# LickStick_v0_3.net
KiCad netlist of a schematic drawn in EAGLE
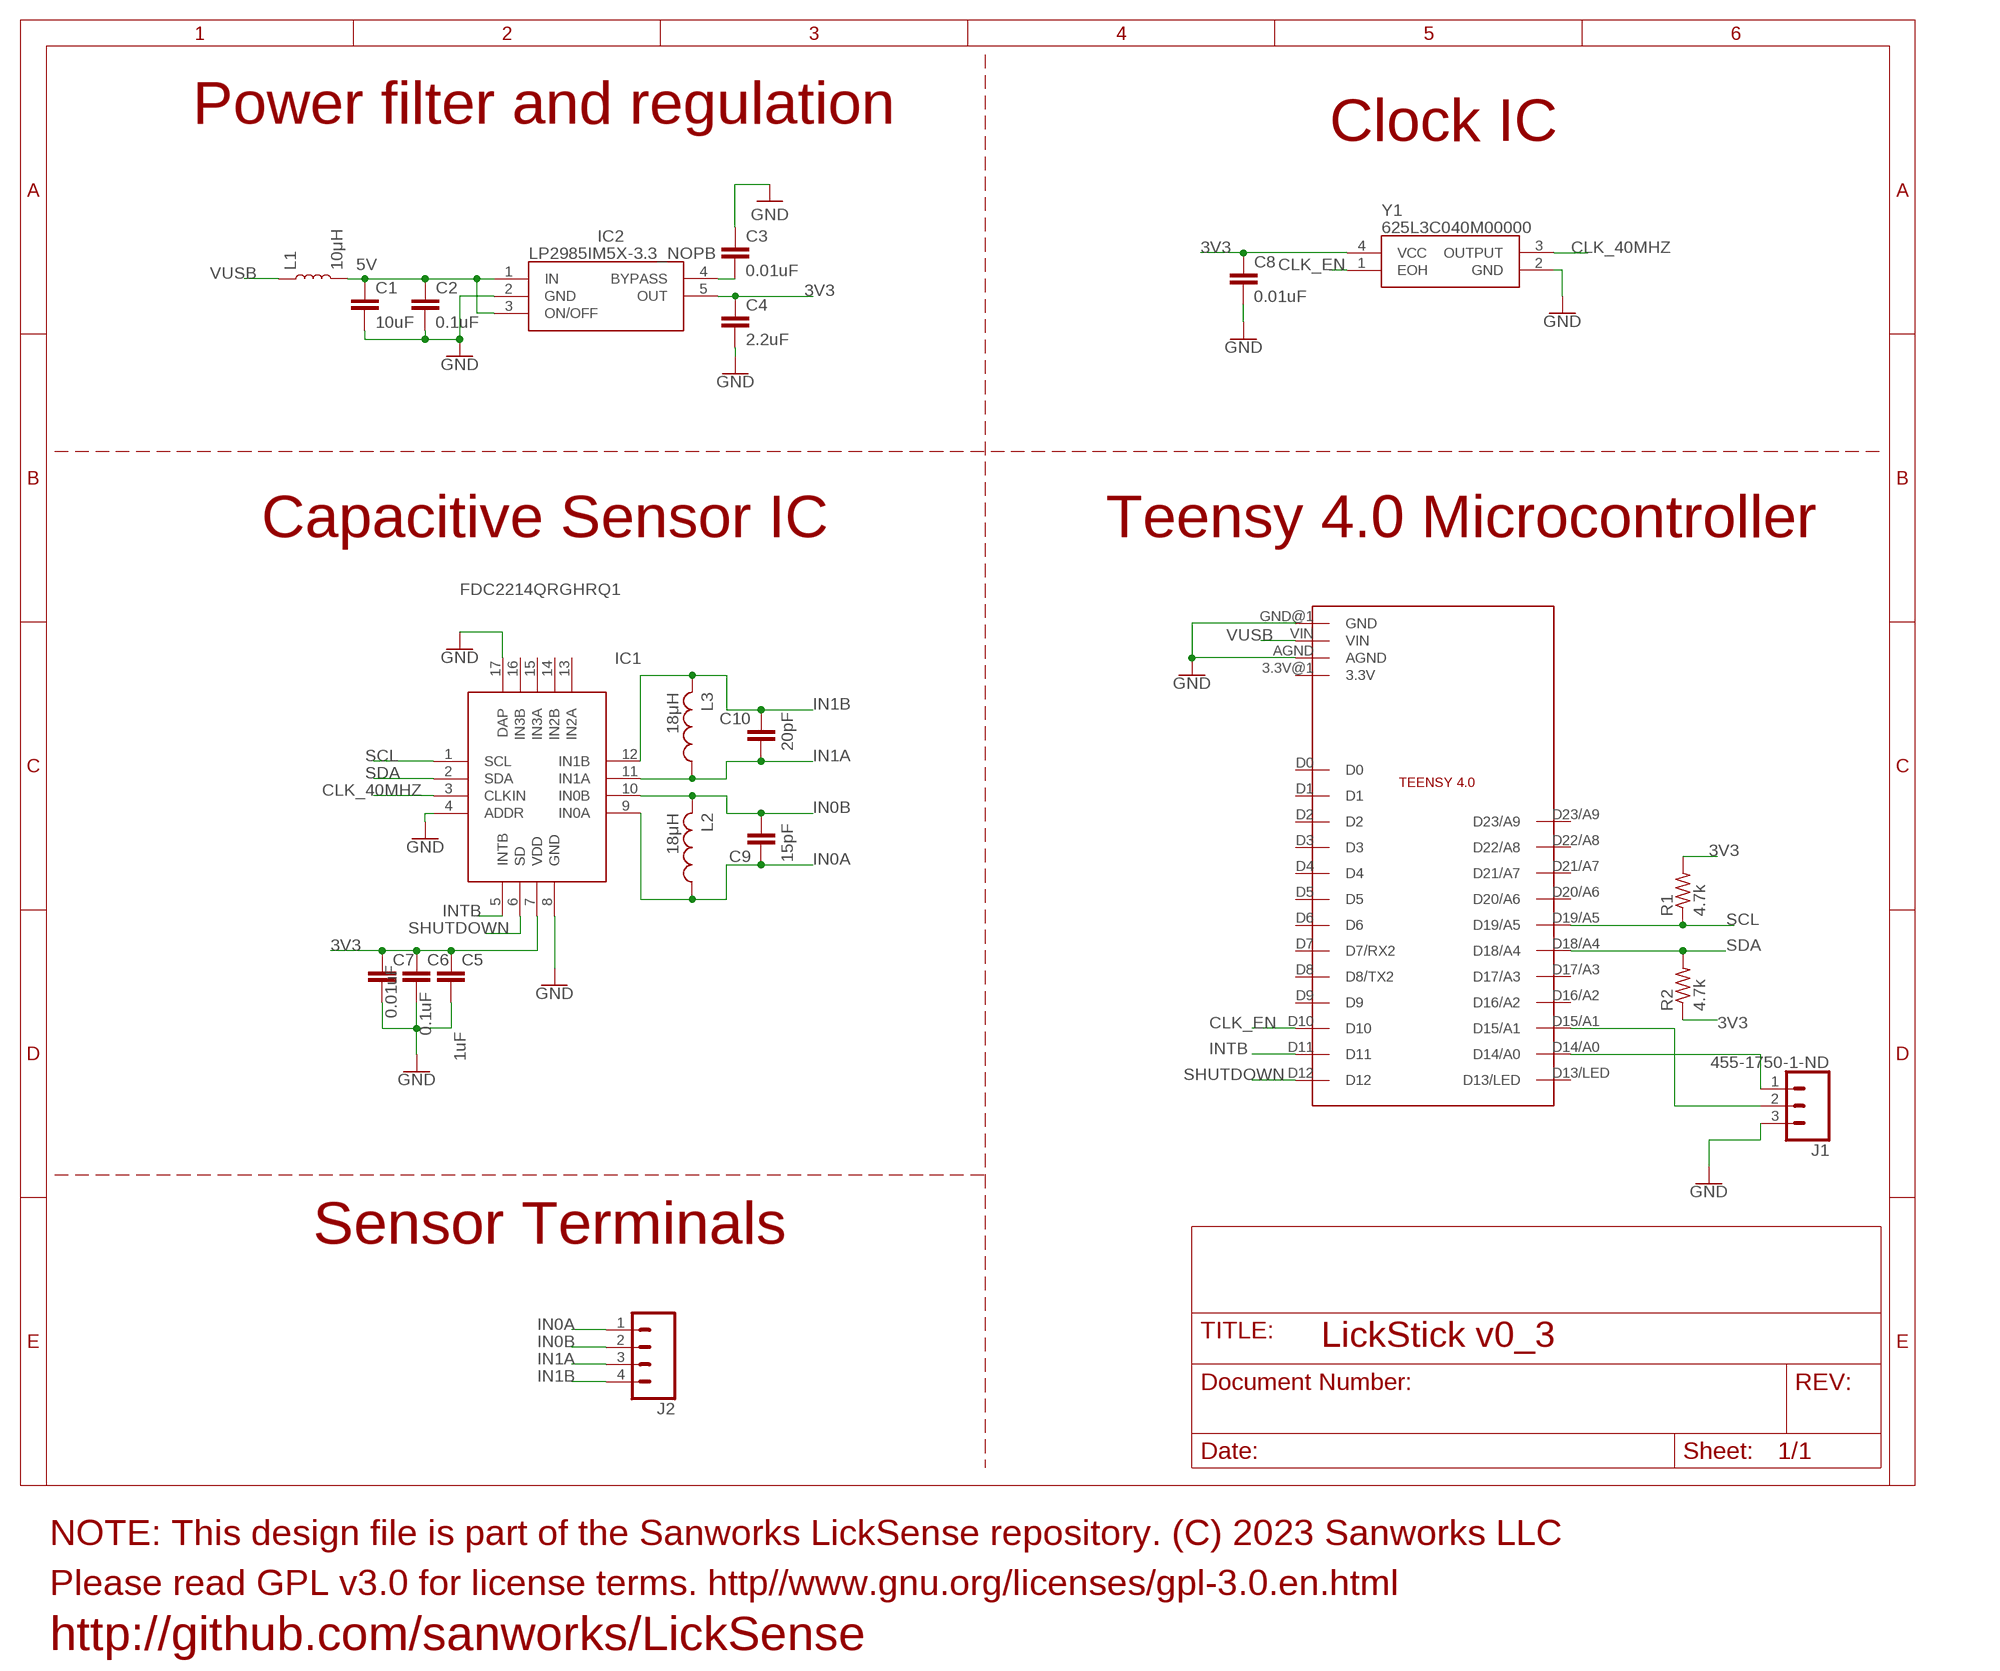
[diagram p0: schematic, sheet 1]

(export (version "E")
  (design (tool "Eeschema 10.0.6"))
  (components
    (comp (ref "C1")
      (value "10uF")
      (footprint "eagle-import:0805")
      (libsource (lib "eagle-import") (part "10UF-0805-10V-10%"))
    )
    (comp (ref "C2")
      (value "0.1uF")
      (footprint "eagle-import:0805")
      (libsource (lib "eagle-import") (part "1.0UF-0805-25V-(+80/-20%)"))
    )
    (comp (ref "C3")
      (value "0.01uF")
      (footprint "eagle-import:0805")
      (libsource (lib "eagle-import") (part "1.0UF-0805-25V-(+80/-20%)"))
    )
    (comp (ref "C4")
      (value "2.2uF")
      (footprint "eagle-import:0805")
      (libsource (lib "eagle-import") (part "1.0UF-0805-25V-(+80/-20%)"))
    )
    (comp (ref "C5")
      (value "1uF")
      (footprint "eagle-import:0805")
      (libsource (lib "eagle-import") (part "1.0UF-0805-25V-(+80/-20%)"))
    )
    (comp (ref "C6")
      (value "0.1uF")
      (footprint "eagle-import:0805")
      (libsource (lib "eagle-import") (part "1.0UF-0805-25V-(+80/-20%)"))
    )
    (comp (ref "C7")
      (value "0.01uF")
      (footprint "eagle-import:0805")
      (libsource (lib "eagle-import") (part "1.0UF-0805-25V-(+80/-20%)"))
    )
    (comp (ref "C8")
      (value "0.01uF")
      (footprint "eagle-import:0805")
      (libsource (lib "eagle-import") (part "1.0UF-0805-25V-(+80/-20%)"))
    )
    (comp (ref "C9")
      (value "15pF")
      (footprint "eagle-import:0805")
      (libsource (lib "eagle-import") (part "1.0UF-0805-25V-(+80/-20%)"))
    )
    (comp (ref "C10")
      (value "20pF")
      (footprint "eagle-import:0805")
      (libsource (lib "eagle-import") (part "1.0UF-0805-25V-(+80/-20%)"))
    )
    (comp (ref "IC1")
      (value "FDC2214QRGHRQ1")
      (footprint "eagle-import:QFN50P400X400X80-17N")
      (fields (field (name "MOUSER_PART_NUMBER") "595-FDC2214QRGHRQ1"))
      (libsource (lib "eagle-import") (part "FDC2214QRGHRQ1"))
    )
    (comp (ref "IC2")
      (value "LP2985IM5X-3.3_NOPB")
      (footprint "eagle-import:SOT95P280X145-5N")
      (fields
        (field (name "MANUFACTURER_PART_NUMBER") "LP2985IM5X-3.3/NOPB")
        (field (name "MOUSER_PART_NUMBER") "926-LP2985IM5X33NOPB")
      )
      (libsource (lib "eagle-import") (part "LP2985IM5X-3.3_NOPB"))
    )
    (comp (ref "J1")
      (value "455-1750-1-ND")
      (footprint "eagle-import:1X03")
      (libsource (lib "eagle-import") (part "CONN_03"))
    )
    (comp (ref "J2")
      (value "CONN_04PTH")
      (footprint "eagle-import:1X04")
      (libsource (lib "eagle-import") (part "CONN_04PTH"))
    )
    (comp (ref "L1")
      (value "10μH")
      (footprint "eagle-import:0806")
      (libsource (lib "eagle-import") (part "2.2μH_SHIELDED_INDUCTOR"))
    )
    (comp (ref "L2")
      (value "18μH")
      (footprint "eagle-import:L3225P")
      (libsource (lib "eagle-import") (part "L-USL3225P"))
    )
    (comp (ref "L3")
      (value "18μH")
      (footprint "eagle-import:L3225P")
      (libsource (lib "eagle-import") (part "L-USL3225P"))
    )
    (comp (ref "MC1")
      (value "TEENSY4.0_SIMPLE_NO_VUSB")
      (footprint "eagle-import:TEENSY4.0_SIMPLE_NO_VUSB")
      (libsource (lib "eagle-import") (part "TEENSY4.0_SIMPLE_NO_VUSB"))
    )
    (comp (ref "R1")
      (value "4.7k")
      (footprint "eagle-import:R0805")
      (libsource (lib "eagle-import") (part "R-US_R0805"))
    )
    (comp (ref "R2")
      (value "4.7k")
      (footprint "eagle-import:R0805")
      (libsource (lib "eagle-import") (part "R-US_R0805"))
    )
    (comp (ref "Y1")
      (value "625L3C040M00000")
      (footprint "eagle-import:625L3C040M00000")
      (fields (field (name "MOUSER_PART_NUMBER") "774-625L3C040M00000"))
      (libsource (lib "eagle-import") (part "625L3C040M00000"))
    )
  )
  (nets
    (net (code "1") (name "/3V3") (class "Default")
      (node (ref "C4") (pin "1") (pinfunction "1_1") (pintype "passive"))
      (node (ref "C5") (pin "1") (pinfunction "1_1") (pintype "passive"))
      (node (ref "C6") (pin "1") (pinfunction "1_1") (pintype "passive"))
      (node (ref "C7") (pin "1") (pinfunction "1_1") (pintype "passive"))
      (node (ref "C8") (pin "1") (pinfunction "1_1") (pintype "passive"))
      (node (ref "IC1") (pin "7") (pinfunction "VDD_7") (pintype "bidirectional"))
      (node (ref "IC2") (pin "5") (pinfunction "OUT_5") (pintype "bidirectional"))
      (node (ref "R1") (pin "2") (pinfunction "2_2") (pintype "passive"))
      (node (ref "R2") (pin "1") (pinfunction "1_1") (pintype "passive"))
      (node (ref "Y1") (pin "4") (pinfunction "VCC_4") (pintype "bidirectional"))
    )
    (net (code "2") (name "/5V") (class "Default")
      (node (ref "C1") (pin "1") (pinfunction "1_1") (pintype "passive"))
      (node (ref "C2") (pin "1") (pinfunction "1_1") (pintype "passive"))
      (node (ref "IC2") (pin "1") (pinfunction "IN_1") (pintype "bidirectional"))
      (node (ref "IC2") (pin "3") (pinfunction "ON/OFF_3") (pintype "bidirectional"))
      (node (ref "L1") (pin "2") (pinfunction "2_2") (pintype "passive"))
    )
    (net (code "3") (name "/CLK_40MHZ") (class "Default")
      (node (ref "IC1") (pin "3") (pinfunction "CLKIN_3") (pintype "bidirectional"))
      (node (ref "Y1") (pin "3") (pinfunction "OUTPUT_3") (pintype "bidirectional"))
    )
    (net (code "4") (name "/CLK_EN") (class "Default")
      (node (ref "MC1") (pin "D10") (pinfunction "D10_D10") (pintype "bidirectional"))
      (node (ref "Y1") (pin "1") (pinfunction "EOH_1") (pintype "bidirectional"))
    )
    (net (code "5") (name "/IN0A") (class "Default")
      (node (ref "C9") (pin "1") (pinfunction "1_1") (pintype "passive"))
      (node (ref "IC1") (pin "9") (pinfunction "IN0A_9") (pintype "bidirectional"))
      (node (ref "J2") (pin "1") (pinfunction "1_1") (pintype "passive"))
      (node (ref "L2") (pin "1") (pinfunction "1_1") (pintype "passive"))
    )
    (net (code "6") (name "/IN0B") (class "Default")
      (node (ref "C9") (pin "2") (pinfunction "2_2") (pintype "passive"))
      (node (ref "IC1") (pin "10") (pinfunction "IN0B_10") (pintype "bidirectional"))
      (node (ref "J2") (pin "2") (pinfunction "2_2") (pintype "passive"))
      (node (ref "L2") (pin "2") (pinfunction "2_2") (pintype "passive"))
    )
    (net (code "7") (name "/IN1A") (class "Default")
      (node (ref "C10") (pin "1") (pinfunction "1_1") (pintype "passive"))
      (node (ref "IC1") (pin "11") (pinfunction "IN1A_11") (pintype "bidirectional"))
      (node (ref "J2") (pin "3") (pinfunction "3_3") (pintype "passive"))
      (node (ref "L3") (pin "1") (pinfunction "1_1") (pintype "passive"))
    )
    (net (code "8") (name "/IN1B") (class "Default")
      (node (ref "C10") (pin "2") (pinfunction "2_2") (pintype "passive"))
      (node (ref "IC1") (pin "12") (pinfunction "IN1B_12") (pintype "bidirectional"))
      (node (ref "J2") (pin "4") (pinfunction "4_4") (pintype "passive"))
      (node (ref "L3") (pin "2") (pinfunction "2_2") (pintype "passive"))
    )
    (net (code "9") (name "/INTB") (class "Default")
      (node (ref "IC1") (pin "5") (pinfunction "INTB_5") (pintype "bidirectional"))
      (node (ref "MC1") (pin "D11") (pinfunction "D11_D11") (pintype "bidirectional"))
    )
    (net (code "10") (name "/SCL") (class "Default")
      (node (ref "IC1") (pin "1") (pinfunction "SCL_1") (pintype "bidirectional"))
      (node (ref "MC1") (pin "D19/A5") (pinfunction "D19/A5_D19/A5") (pintype "bidirectional"))
      (node (ref "R1") (pin "1") (pinfunction "1_1") (pintype "passive"))
    )
    (net (code "11") (name "/SDA") (class "Default")
      (node (ref "IC1") (pin "2") (pinfunction "SDA_2") (pintype "bidirectional"))
      (node (ref "MC1") (pin "D18/A4") (pinfunction "D18/A4_D18/A4") (pintype "bidirectional"))
      (node (ref "R2") (pin "2") (pinfunction "2_2") (pintype "passive"))
    )
    (net (code "12") (name "/SHUTDOWN") (class "Default")
      (node (ref "IC1") (pin "6") (pinfunction "SD_6") (pintype "bidirectional"))
      (node (ref "MC1") (pin "D12") (pinfunction "D12_D12") (pintype "bidirectional"))
    )
    (net (code "13") (name "/VUSB") (class "Default")
      (node (ref "L1") (pin "1") (pinfunction "1_1") (pintype "passive"))
      (node (ref "MC1") (pin "VIN") (pinfunction "VIN_VIN") (pintype "bidirectional"))
    )
    (net (code "14") (name "GND") (class "Default")
      (node (ref "C1") (pin "2") (pinfunction "2_2") (pintype "passive"))
      (node (ref "C2") (pin "2") (pinfunction "2_2") (pintype "passive"))
      (node (ref "C3") (pin "1") (pinfunction "1_1") (pintype "passive"))
      (node (ref "C4") (pin "2") (pinfunction "2_2") (pintype "passive"))
      (node (ref "C5") (pin "2") (pinfunction "2_2") (pintype "passive"))
      (node (ref "C6") (pin "2") (pinfunction "2_2") (pintype "passive"))
      (node (ref "C7") (pin "2") (pinfunction "2_2") (pintype "passive"))
      (node (ref "C8") (pin "2") (pinfunction "2_2") (pintype "passive"))
      (node (ref "IC1") (pin "17") (pinfunction "DAP_17") (pintype "bidirectional"))
      (node (ref "IC1") (pin "4") (pinfunction "ADDR_4") (pintype "bidirectional"))
      (node (ref "IC1") (pin "8") (pinfunction "GND_8") (pintype "bidirectional"))
      (node (ref "IC2") (pin "2") (pinfunction "GND_2") (pintype "bidirectional"))
      (node (ref "J1") (pin "3") (pinfunction "3_3") (pintype "passive"))
      (node (ref "MC1") (pin "AGND") (pinfunction "AGND_AGND") (pintype "bidirectional"))
      (node (ref "MC1") (pin "GND@1") (pinfunction "GND_GND@1") (pintype "bidirectional"))
      (node (ref "Y1") (pin "2") (pinfunction "GND_2") (pintype "bidirectional"))
    )
    (net (code "15") (name "Net-(IC2-BYPASS)") (class "Default")
      (node (ref "C3") (pin "2") (pinfunction "2_2") (pintype "passive"))
      (node (ref "IC2") (pin "4") (pinfunction "BYPASS_4") (pintype "bidirectional"))
    )
    (net (code "16") (name "Net-(J1-Pad1)") (class "Default")
      (node (ref "J1") (pin "1") (pinfunction "1_1") (pintype "passive"))
      (node (ref "MC1") (pin "D14/A0") (pinfunction "D14/A0_D14/A0") (pintype "bidirectional"))
    )
    (net (code "17") (name "Net-(J1-Pad2)") (class "Default")
      (node (ref "J1") (pin "2") (pinfunction "2_2") (pintype "passive"))
      (node (ref "MC1") (pin "D15/A1") (pinfunction "D15/A1_D15/A1") (pintype "bidirectional"))
    )
    (net (code "18") (name "unconnected-(IC1-IN2A-Pad13)") (class "Default")
      (node (ref "IC1") (pin "13") (pinfunction "IN2A_13") (pintype "bidirectional"))
    )
    (net (code "19") (name "unconnected-(IC1-IN2B-Pad14)") (class "Default")
      (node (ref "IC1") (pin "14") (pinfunction "IN2B_14") (pintype "bidirectional"))
    )
    (net (code "20") (name "unconnected-(IC1-IN3A-Pad15)") (class "Default")
      (node (ref "IC1") (pin "15") (pinfunction "IN3A_15") (pintype "bidirectional"))
    )
    (net (code "21") (name "unconnected-(IC1-IN3B-Pad16)") (class "Default")
      (node (ref "IC1") (pin "16") (pinfunction "IN3B_16") (pintype "bidirectional"))
    )
    (net (code "22") (name "unconnected-(MC1-3.3V-Pad3.3V@1)") (class "Default")
      (node (ref "MC1") (pin "3.3V@1") (pinfunction "3.3V_3.3V@1") (pintype "bidirectional"))
    )
    (net (code "23") (name "unconnected-(MC1-D7{slash}RX2-PadD7)") (class "Default")
      (node (ref "MC1") (pin "D7") (pinfunction "D7/RX2_D7") (pintype "bidirectional"))
    )
    (net (code "24") (name "unconnected-(MC1-D8{slash}TX2-PadD8)") (class "Default")
      (node (ref "MC1") (pin "D8") (pinfunction "D8/TX2_D8") (pintype "bidirectional"))
    )
    (net (code "25") (name "unconnected-(MC1-PadD0)") (class "Default")
      (node (ref "MC1") (pin "D0") (pinfunction "D0_D0") (pintype "bidirectional"))
    )
    (net (code "26") (name "unconnected-(MC1-PadD1)") (class "Default")
      (node (ref "MC1") (pin "D1") (pinfunction "D1_D1") (pintype "bidirectional"))
    )
    (net (code "27") (name "unconnected-(MC1-PadD2)") (class "Default")
      (node (ref "MC1") (pin "D2") (pinfunction "D2_D2") (pintype "bidirectional"))
    )
    (net (code "28") (name "unconnected-(MC1-PadD3)") (class "Default")
      (node (ref "MC1") (pin "D3") (pinfunction "D3_D3") (pintype "bidirectional"))
    )
    (net (code "29") (name "unconnected-(MC1-PadD4)") (class "Default")
      (node (ref "MC1") (pin "D4") (pinfunction "D4_D4") (pintype "bidirectional"))
    )
    (net (code "30") (name "unconnected-(MC1-PadD5)") (class "Default")
      (node (ref "MC1") (pin "D5") (pinfunction "D5_D5") (pintype "bidirectional"))
    )
    (net (code "31") (name "unconnected-(MC1-PadD6)") (class "Default")
      (node (ref "MC1") (pin "D6") (pinfunction "D6_D6") (pintype "bidirectional"))
    )
    (net (code "32") (name "unconnected-(MC1-PadD9)") (class "Default")
      (node (ref "MC1") (pin "D9") (pinfunction "D9_D9") (pintype "bidirectional"))
    )
    (net (code "33") (name "unconnected-(MC1-PadD13{slash}LED)") (class "Default")
      (node (ref "MC1") (pin "D13/LED") (pinfunction "D13/LED_D13/LED") (pintype "bidirectional"))
    )
    (net (code "34") (name "unconnected-(MC1-PadD16{slash}A2)") (class "Default")
      (node (ref "MC1") (pin "D16/A2") (pinfunction "D16/A2_D16/A2") (pintype "bidirectional"))
    )
    (net (code "35") (name "unconnected-(MC1-PadD17{slash}A3)") (class "Default")
      (node (ref "MC1") (pin "D17/A3") (pinfunction "D17/A3_D17/A3") (pintype "bidirectional"))
    )
    (net (code "36") (name "unconnected-(MC1-PadD20{slash}A6)") (class "Default")
      (node (ref "MC1") (pin "D20/A6") (pinfunction "D20/A6_D20/A6") (pintype "bidirectional"))
    )
    (net (code "37") (name "unconnected-(MC1-PadD21{slash}A7)") (class "Default")
      (node (ref "MC1") (pin "D21/A7") (pinfunction "D21/A7_D21/A7") (pintype "bidirectional"))
    )
    (net (code "38") (name "unconnected-(MC1-PadD22{slash}A8)") (class "Default")
      (node (ref "MC1") (pin "D22/A8") (pinfunction "D22/A8_D22/A8") (pintype "bidirectional"))
    )
    (net (code "39") (name "unconnected-(MC1-PadD23{slash}A9)") (class "Default")
      (node (ref "MC1") (pin "D23/A9") (pinfunction "D23/A9_D23/A9") (pintype "bidirectional"))
    )
  )
)
